# ATmega128RFA1-DevBoard_routed.net
KiCad netlist of a schematic drawn in EAGLE
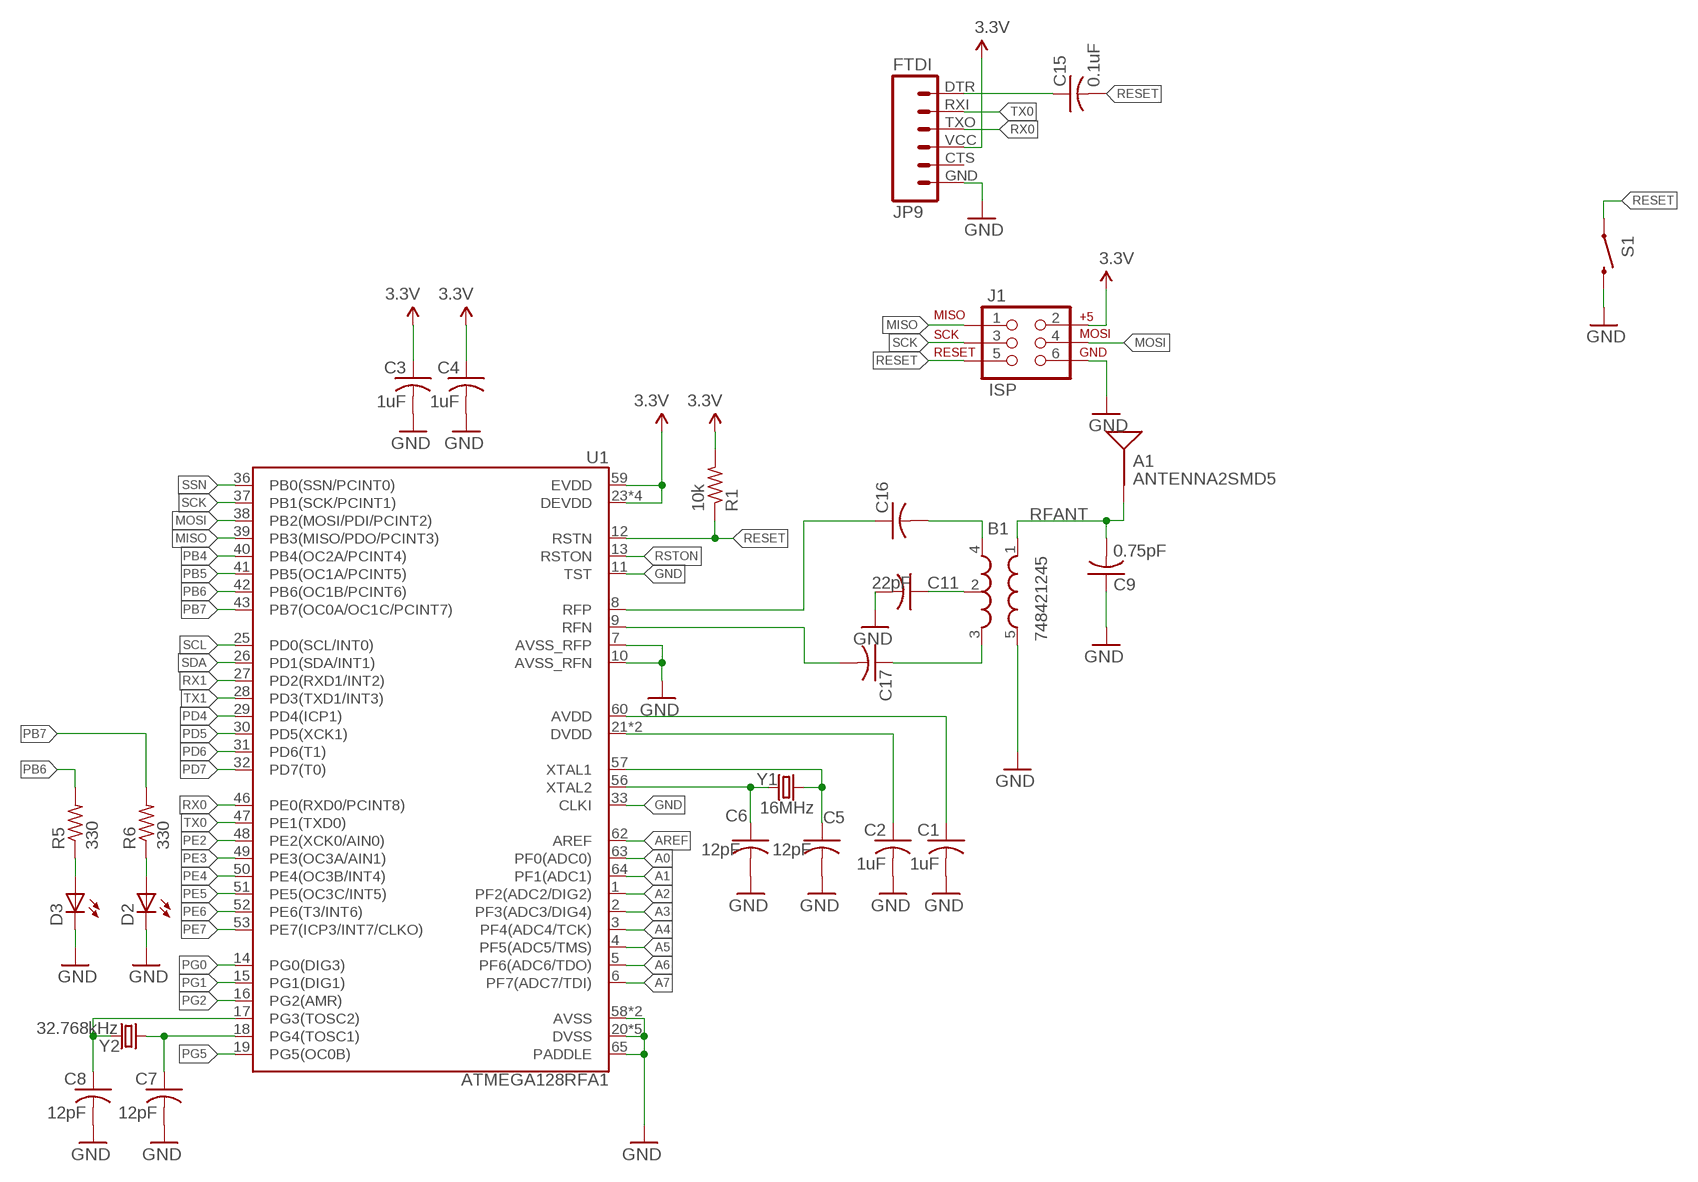
[diagram p0: schematic, sheet 1]

(export (version "E")
  (design (tool "Eeschema 10.0.6"))
  (components
    (comp (ref "A1")
      (value "ANTENNA2SMD5")
      (footprint "eagle-import:ANTENNA-CHIP5")
      (libsource (lib "eagle-import") (part "ANTENNA2SMD5"))
    )
    (comp (ref "B1")
      (value "748421245")
      (footprint "eagle-import:BALUN")
      (libsource (lib "eagle-import") (part "BALUN0805"))
    )
    (comp (ref "C1")
      (value "1uF")
      (footprint "eagle-import:C0805")
      (libsource (lib "eagle-import") (part "C-USC0805"))
    )
    (comp (ref "C2")
      (value "1uF")
      (footprint "eagle-import:C0805")
      (libsource (lib "eagle-import") (part "C-USC0805"))
    )
    (comp (ref "C3")
      (value "1uF")
      (footprint "eagle-import:C0805")
      (libsource (lib "eagle-import") (part "C-USC0805"))
    )
    (comp (ref "C4")
      (value "1uF")
      (footprint "eagle-import:C0805")
      (libsource (lib "eagle-import") (part "C-USC0805"))
    )
    (comp (ref "C5")
      (value "12pF")
      (footprint "eagle-import:C0805")
      (libsource (lib "eagle-import") (part "C-USC0805"))
    )
    (comp (ref "C6")
      (value "12pF")
      (footprint "eagle-import:C0805")
      (libsource (lib "eagle-import") (part "C-USC0805"))
    )
    (comp (ref "C7")
      (value "12pF")
      (footprint "eagle-import:C0805")
      (libsource (lib "eagle-import") (part "C-USC0805"))
    )
    (comp (ref "C8")
      (value "12pF")
      (footprint "eagle-import:C0805")
      (libsource (lib "eagle-import") (part "C-USC0805"))
    )
    (comp (ref "C9")
      (value "0.75pF")
      (footprint "eagle-import:C0805")
      (libsource (lib "eagle-import") (part "C-USC0805"))
    )
    (comp (ref "C11")
      (value "22pF")
      (footprint "eagle-import:C0805")
      (libsource (lib "eagle-import") (part "C-USC0805"))
    )
    (comp (ref "C15")
      (value "0.1uF")
      (footprint "eagle-import:C0805")
      (libsource (lib "eagle-import") (part "C-USC0805"))
    )
    (comp (ref "C16")
      (value "C-USC0805")
      (footprint "eagle-import:C0805")
      (libsource (lib "eagle-import") (part "C-USC0805"))
    )
    (comp (ref "C17")
      (value "C-USC0805")
      (footprint "eagle-import:C0805")
      (libsource (lib "eagle-import") (part "C-USC0805"))
    )
    (comp (ref "D2")
      (value "LED5MM")
      (footprint "eagle-import:LED5MM")
      (libsource (lib "eagle-import") (part "LED5MM"))
    )
    (comp (ref "D3")
      (value "LED5MM")
      (footprint "eagle-import:LED5MM")
      (libsource (lib "eagle-import") (part "LED5MM"))
    )
    (comp (ref "J1")
      (value "ISP")
      (footprint "eagle-import:2X3-NS")
      (libsource (lib "eagle-import") (part "AVR_SPI_PRG_6NS"))
    )
    (comp (ref "JP9")
      (value "FTDI")
      (footprint "eagle-import:FTDI_BASIC")
      (libsource (lib "eagle-import") (part "FTDI_BASICPTH"))
    )
    (comp (ref "R1")
      (value "10k")
      (footprint "eagle-import:R0805")
      (libsource (lib "eagle-import") (part "R-US_R0805"))
    )
    (comp (ref "R5")
      (value "330")
      (footprint "eagle-import:R0805")
      (libsource (lib "eagle-import") (part "R-US_R0805"))
    )
    (comp (ref "R6")
      (value "330")
      (footprint "eagle-import:R0805")
      (libsource (lib "eagle-import") (part "R-US_R0805"))
    )
    (comp (ref "S1")
      (value "SWITCH-MOMENTARY-2SMD")
      (footprint "eagle-import:TACTILE_SWITCH_SMD")
      (libsource (lib "eagle-import") (part "SWITCH-MOMENTARY-2SMD"))
    )
    (comp (ref "U1")
      (value "ATMEGA128RFA1")
      (footprint "eagle-import:QFN-64")
      (libsource (lib "eagle-import") (part "ATMEGA128RFA1"))
    )
    (comp (ref "Y1")
      (value "16MHz")
      (footprint "eagle-import:CRYSTAL-SMD-5X3")
      (libsource (lib "eagle-import") (part "CRYSTAL5X3"))
    )
    (comp (ref "Y2")
      (value "32.768kHz")
      (footprint "eagle-import:CRYSTAL-32KHZ-SMD")
      (libsource (lib "eagle-import") (part "CRYSTAL32-SMD"))
    )
  )
  (nets
    (net (code "1") (name "/RFANT") (class "Default")
      (node (ref "A1") (pin "FEED") (pinfunction "SIGNAL_FEED") (pintype "bidirectional"))
      (node (ref "B1") (pin "1") (pinfunction "IN_1") (pintype "bidirectional"))
      (node (ref "C9") (pin "2") (pinfunction "2_2") (pintype "passive"))
    )
    (net (code "2") (name "3.3V") (class "Default")
      (node (ref "C3") (pin "1") (pinfunction "1_1") (pintype "passive"))
      (node (ref "C4") (pin "1") (pinfunction "1_1") (pintype "passive"))
      (node (ref "J1") (pin "2") (pinfunction "2_2") (pintype "passive"))
      (node (ref "JP9") (pin "VCC") (pinfunction "4_VCC") (pintype "passive"))
      (node (ref "R1") (pin "2") (pinfunction "2_2") (pintype "passive"))
      (node (ref "U1") (pin "23") (pinfunction "DEVDD_23") (pintype "bidirectional"))
      (node (ref "U1") (pin "34") (pinfunction "DEVDD_34") (pintype "bidirectional"))
      (node (ref "U1") (pin "44") (pinfunction "DEVDD_44") (pintype "bidirectional"))
      (node (ref "U1") (pin "54") (pinfunction "DEVDD_54") (pintype "bidirectional"))
      (node (ref "U1") (pin "59") (pinfunction "EVDD_59") (pintype "bidirectional"))
    )
    (net (code "3") (name "A0") (class "Default")
      (node (ref "U1") (pin "63") (pinfunction "PF0(ADC0)_63") (pintype "bidirectional"))
    )
    (net (code "4") (name "A1") (class "Default")
      (node (ref "U1") (pin "64") (pinfunction "PF1(ADC1)_64") (pintype "bidirectional"))
    )
    (net (code "5") (name "A2") (class "Default")
      (node (ref "U1") (pin "1") (pinfunction "PF2(ADC2/DIG2)_1") (pintype "bidirectional"))
    )
    (net (code "6") (name "A3") (class "Default")
      (node (ref "U1") (pin "2") (pinfunction "PF3(ADC3/DIG4)_2") (pintype "bidirectional"))
    )
    (net (code "7") (name "A4") (class "Default")
      (node (ref "U1") (pin "3") (pinfunction "PF4(ADC4/TCK)_3") (pintype "bidirectional"))
    )
    (net (code "8") (name "A5") (class "Default")
      (node (ref "U1") (pin "4") (pinfunction "PF5(ADC5/TMS)_4") (pintype "bidirectional"))
    )
    (net (code "9") (name "A6") (class "Default")
      (node (ref "U1") (pin "5") (pinfunction "PF6(ADC6/TDO)_5") (pintype "bidirectional"))
    )
    (net (code "10") (name "A7") (class "Default")
      (node (ref "U1") (pin "6") (pinfunction "PF7(ADC7/TDI)_6") (pintype "bidirectional"))
    )
    (net (code "11") (name "AREF") (class "Default")
      (node (ref "U1") (pin "62") (pinfunction "AREF_62") (pintype "bidirectional"))
    )
    (net (code "12") (name "GND") (class "Default")
      (node (ref "B1") (pin "5") (pinfunction "GND_5") (pintype "bidirectional"))
      (node (ref "C1") (pin "2") (pinfunction "2_2") (pintype "passive"))
      (node (ref "C11") (pin "2") (pinfunction "2_2") (pintype "passive"))
      (node (ref "C2") (pin "2") (pinfunction "2_2") (pintype "passive"))
      (node (ref "C3") (pin "2") (pinfunction "2_2") (pintype "passive"))
      (node (ref "C4") (pin "2") (pinfunction "2_2") (pintype "passive"))
      (node (ref "C5") (pin "2") (pinfunction "2_2") (pintype "passive"))
      (node (ref "C6") (pin "2") (pinfunction "2_2") (pintype "passive"))
      (node (ref "C7") (pin "2") (pinfunction "2_2") (pintype "passive"))
      (node (ref "C8") (pin "2") (pinfunction "2_2") (pintype "passive"))
      (node (ref "C9") (pin "1") (pinfunction "1_1") (pintype "passive"))
      (node (ref "D2") (pin "K") (pinfunction "C_K") (pintype "passive"))
      (node (ref "D3") (pin "K") (pinfunction "C_K") (pintype "passive"))
      (node (ref "J1") (pin "6") (pinfunction "6_6") (pintype "passive"))
      (node (ref "JP9") (pin "GND") (pinfunction "6_GND") (pintype "passive"))
      (node (ref "S1") (pin "3") (pinfunction "2_3") (pintype "passive"))
      (node (ref "U1") (pin "10") (pinfunction "AVSS_RFN_10") (pintype "bidirectional"))
      (node (ref "U1") (pin "11") (pinfunction "TST_11") (pintype "bidirectional"))
      (node (ref "U1") (pin "20") (pinfunction "DVSS_20") (pintype "bidirectional"))
      (node (ref "U1") (pin "24") (pinfunction "DVSS_24") (pintype "bidirectional"))
      (node (ref "U1") (pin "33") (pinfunction "CLKI_33") (pintype "bidirectional"))
      (node (ref "U1") (pin "35") (pinfunction "DVSS_35") (pintype "bidirectional"))
      (node (ref "U1") (pin "45") (pinfunction "DVSS_45") (pintype "bidirectional"))
      (node (ref "U1") (pin "55") (pinfunction "DVSS_55") (pintype "bidirectional"))
      (node (ref "U1") (pin "58") (pinfunction "AVSS_58") (pintype "bidirectional"))
      (node (ref "U1") (pin "61") (pinfunction "AVSS_61") (pintype "bidirectional"))
      (node (ref "U1") (pin "65") (pinfunction "PADDLE_65") (pintype "bidirectional"))
      (node (ref "U1") (pin "7") (pinfunction "AVSS_RFP_7") (pintype "bidirectional"))
    )
    (net (code "13") (name "MISO") (class "Default")
      (node (ref "J1") (pin "1") (pinfunction "1_1") (pintype "passive"))
      (node (ref "U1") (pin "39") (pinfunction "PB3(MISO/PDO/PCINT3)_39") (pintype "bidirectional"))
    )
    (net (code "14") (name "MOSI") (class "Default")
      (node (ref "J1") (pin "4") (pinfunction "4_4") (pintype "passive"))
      (node (ref "U1") (pin "38") (pinfunction "PB2(MOSI/PDI/PCINT2)_38") (pintype "bidirectional"))
    )
    (net (code "15") (name "Net-(B1-GND-Pad2)") (class "Default")
      (node (ref "B1") (pin "2") (pinfunction "GND_2") (pintype "bidirectional"))
      (node (ref "C11") (pin "1") (pinfunction "1_1") (pintype "passive"))
    )
    (net (code "16") (name "Net-(B1-OUT1)") (class "Default")
      (node (ref "B1") (pin "4") (pinfunction "OUT1_4") (pintype "bidirectional"))
      (node (ref "C16") (pin "2") (pinfunction "2_2") (pintype "passive"))
    )
    (net (code "17") (name "Net-(B1-OUT2)") (class "Default")
      (node (ref "B1") (pin "3") (pinfunction "OUT2_3") (pintype "bidirectional"))
      (node (ref "C17") (pin "1") (pinfunction "1_1") (pintype "passive"))
    )
    (net (code "18") (name "Net-(C2-Pad1)") (class "Default")
      (node (ref "C2") (pin "1") (pinfunction "1_1") (pintype "passive"))
      (node (ref "U1") (pin "21") (pinfunction "DVDD_21") (pintype "bidirectional"))
      (node (ref "U1") (pin "22") (pinfunction "DVDD_22") (pintype "bidirectional"))
    )
    (net (code "19") (name "Net-(D2-PadA)") (class "Default")
      (node (ref "D2") (pin "A") (pinfunction "A_A") (pintype "passive"))
      (node (ref "R6") (pin "1") (pinfunction "1_1") (pintype "passive"))
    )
    (net (code "20") (name "Net-(D3-PadA)") (class "Default")
      (node (ref "D3") (pin "A") (pinfunction "A_A") (pintype "passive"))
      (node (ref "R5") (pin "1") (pinfunction "1_1") (pintype "passive"))
    )
    (net (code "21") (name "Net-(JP9-1)") (class "Default")
      (node (ref "C15") (pin "1") (pinfunction "1_1") (pintype "passive"))
      (node (ref "JP9") (pin "DTR") (pinfunction "1_DTR") (pintype "passive"))
    )
    (net (code "22") (name "Net-(U1-AVDD)") (class "Default")
      (node (ref "C1") (pin "1") (pinfunction "1_1") (pintype "passive"))
      (node (ref "U1") (pin "60") (pinfunction "AVDD_60") (pintype "bidirectional"))
    )
    (net (code "23") (name "Net-(U1-PG3(TOSC2))") (class "Default")
      (node (ref "C8") (pin "1") (pinfunction "1_1") (pintype "passive"))
      (node (ref "U1") (pin "17") (pinfunction "PG3(TOSC2)_17") (pintype "bidirectional"))
      (node (ref "Y2") (pin "X2") (pinfunction "2_X2") (pintype "passive"))
    )
    (net (code "24") (name "Net-(U1-PG4(TOSC1))") (class "Default")
      (node (ref "C7") (pin "1") (pinfunction "1_1") (pintype "passive"))
      (node (ref "U1") (pin "18") (pinfunction "PG4(TOSC1)_18") (pintype "bidirectional"))
      (node (ref "Y2") (pin "X1") (pinfunction "1_X1") (pintype "passive"))
    )
    (net (code "25") (name "Net-(U1-RFN)") (class "Default")
      (node (ref "C17") (pin "2") (pinfunction "2_2") (pintype "passive"))
      (node (ref "U1") (pin "9") (pinfunction "RFN_9") (pintype "bidirectional"))
    )
    (net (code "26") (name "Net-(U1-RFP)") (class "Default")
      (node (ref "C16") (pin "1") (pinfunction "1_1") (pintype "passive"))
      (node (ref "U1") (pin "8") (pinfunction "RFP_8") (pintype "bidirectional"))
    )
    (net (code "27") (name "Net-(U1-XTAL1)") (class "Default")
      (node (ref "C5") (pin "1") (pinfunction "1_1") (pintype "passive"))
      (node (ref "U1") (pin "57") (pinfunction "XTAL1_57") (pintype "bidirectional"))
      (node (ref "Y1") (pin "3") (pinfunction "2_3") (pintype "passive"))
    )
    (net (code "28") (name "Net-(U1-XTAL2)") (class "Default")
      (node (ref "C6") (pin "1") (pinfunction "1_1") (pintype "passive"))
      (node (ref "U1") (pin "56") (pinfunction "XTAL2_56") (pintype "bidirectional"))
      (node (ref "Y1") (pin "1") (pinfunction "1_1") (pintype "passive"))
    )
    (net (code "29") (name "PB4") (class "Default")
      (node (ref "U1") (pin "40") (pinfunction "PB4(OC2A/PCINT4)_40") (pintype "bidirectional"))
    )
    (net (code "30") (name "PB5") (class "Default")
      (node (ref "U1") (pin "41") (pinfunction "PB5(OC1A/PCINT5)_41") (pintype "bidirectional"))
    )
    (net (code "31") (name "PB6") (class "Default")
      (node (ref "R5") (pin "2") (pinfunction "2_2") (pintype "passive"))
      (node (ref "U1") (pin "42") (pinfunction "PB6(OC1B/PCINT6)_42") (pintype "bidirectional"))
    )
    (net (code "32") (name "PB7") (class "Default")
      (node (ref "R6") (pin "2") (pinfunction "2_2") (pintype "passive"))
      (node (ref "U1") (pin "43") (pinfunction "PB7(OC0A/OC1C/PCINT7)_43") (pintype "bidirectional"))
    )
    (net (code "33") (name "PD4") (class "Default")
      (node (ref "U1") (pin "29") (pinfunction "PD4(ICP1)_29") (pintype "bidirectional"))
    )
    (net (code "34") (name "PD5") (class "Default")
      (node (ref "U1") (pin "30") (pinfunction "PD5(XCK1)_30") (pintype "bidirectional"))
    )
    (net (code "35") (name "PD6") (class "Default")
      (node (ref "U1") (pin "31") (pinfunction "PD6(T1)_31") (pintype "bidirectional"))
    )
    (net (code "36") (name "PD7") (class "Default")
      (node (ref "U1") (pin "32") (pinfunction "PD7(T0)_32") (pintype "bidirectional"))
    )
    (net (code "37") (name "PE2") (class "Default")
      (node (ref "U1") (pin "48") (pinfunction "PE2(XCK0/AIN0)_48") (pintype "bidirectional"))
    )
    (net (code "38") (name "PE3") (class "Default")
      (node (ref "U1") (pin "49") (pinfunction "PE3(OC3A/AIN1)_49") (pintype "bidirectional"))
    )
    (net (code "39") (name "PE4") (class "Default")
      (node (ref "U1") (pin "50") (pinfunction "PE4(OC3B/INT4)_50") (pintype "bidirectional"))
    )
    (net (code "40") (name "PE5") (class "Default")
      (node (ref "U1") (pin "51") (pinfunction "PE5(OC3C/INT5)_51") (pintype "bidirectional"))
    )
    (net (code "41") (name "PE6") (class "Default")
      (node (ref "U1") (pin "52") (pinfunction "PE6(T3/INT6)_52") (pintype "bidirectional"))
    )
    (net (code "42") (name "PE7") (class "Default")
      (node (ref "U1") (pin "53") (pinfunction "PE7(ICP3/INT7/CLKO)_53") (pintype "bidirectional"))
    )
    (net (code "43") (name "PG0") (class "Default")
      (node (ref "U1") (pin "14") (pinfunction "PG0(DIG3)_14") (pintype "bidirectional"))
    )
    (net (code "44") (name "PG1") (class "Default")
      (node (ref "U1") (pin "15") (pinfunction "PG1(DIG1)_15") (pintype "bidirectional"))
    )
    (net (code "45") (name "PG2") (class "Default")
      (node (ref "U1") (pin "16") (pinfunction "PG2(AMR)_16") (pintype "bidirectional"))
    )
    (net (code "46") (name "PG5") (class "Default")
      (node (ref "U1") (pin "19") (pinfunction "PG5(OC0B)_19") (pintype "bidirectional"))
    )
    (net (code "47") (name "RESET") (class "Default")
      (node (ref "C15") (pin "2") (pinfunction "2_2") (pintype "passive"))
      (node (ref "J1") (pin "5") (pinfunction "5_5") (pintype "passive"))
      (node (ref "R1") (pin "1") (pinfunction "1_1") (pintype "passive"))
      (node (ref "S1") (pin "1") (pinfunction "1_1") (pintype "passive"))
      (node (ref "U1") (pin "12") (pinfunction "RSTN_12") (pintype "bidirectional"))
    )
    (net (code "48") (name "RSTON") (class "Default")
      (node (ref "U1") (pin "13") (pinfunction "RSTON_13") (pintype "bidirectional"))
    )
    (net (code "49") (name "RX0") (class "Default")
      (node (ref "JP9") (pin "TXO") (pinfunction "3_TXO") (pintype "passive"))
      (node (ref "U1") (pin "46") (pinfunction "PE0(RXD0/PCINT8)_46") (pintype "bidirectional"))
    )
    (net (code "50") (name "RX1") (class "Default")
      (node (ref "U1") (pin "27") (pinfunction "PD2(RXD1/INT2)_27") (pintype "bidirectional"))
    )
    (net (code "51") (name "SCK") (class "Default")
      (node (ref "J1") (pin "3") (pinfunction "3_3") (pintype "passive"))
      (node (ref "U1") (pin "37") (pinfunction "PB1(SCK/PCINT1)_37") (pintype "bidirectional"))
    )
    (net (code "52") (name "SCL") (class "Default")
      (node (ref "U1") (pin "25") (pinfunction "PD0(SCL/INT0)_25") (pintype "bidirectional"))
    )
    (net (code "53") (name "SDA") (class "Default")
      (node (ref "U1") (pin "26") (pinfunction "PD1(SDA/INT1)_26") (pintype "bidirectional"))
    )
    (net (code "54") (name "SSN") (class "Default")
      (node (ref "U1") (pin "36") (pinfunction "PB0(SSN/PCINT0)_36") (pintype "bidirectional"))
    )
    (net (code "55") (name "TX0") (class "Default")
      (node (ref "JP9") (pin "RXI") (pinfunction "2_RXI") (pintype "passive"))
      (node (ref "U1") (pin "47") (pinfunction "PE1(TXD0)_47") (pintype "bidirectional"))
    )
    (net (code "56") (name "TX1") (class "Default")
      (node (ref "U1") (pin "28") (pinfunction "PD3(TXD1/INT3)_28") (pintype "bidirectional"))
    )
    (net (code "57") (name "unconnected-(JP9-5-PadCTS)") (class "Default")
      (node (ref "JP9") (pin "CTS") (pinfunction "5_CTS") (pintype "passive"))
    )
  )
)
